# S8254A-HY2213-4S.net
KiCad netlist of a schematic drawn in EAGLE
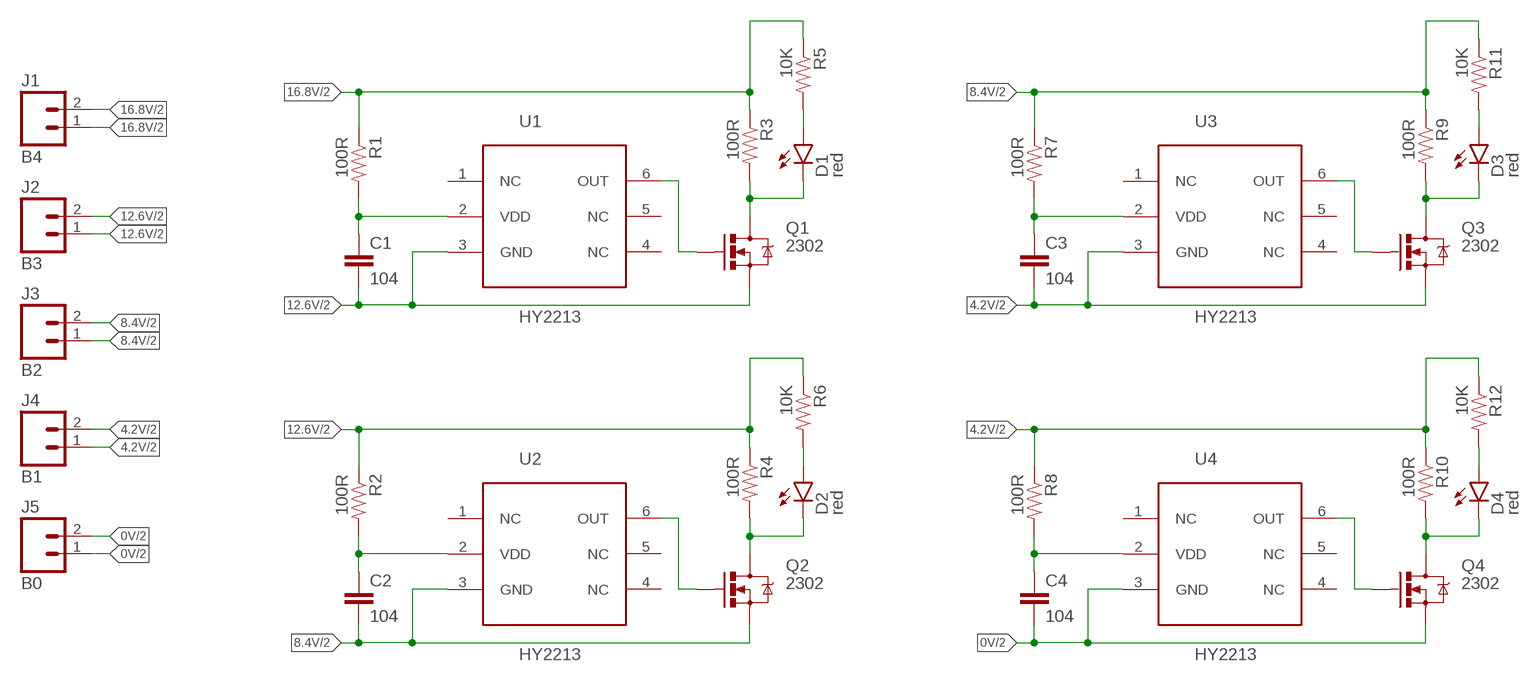
[diagram p0: schematic, sheet 1]
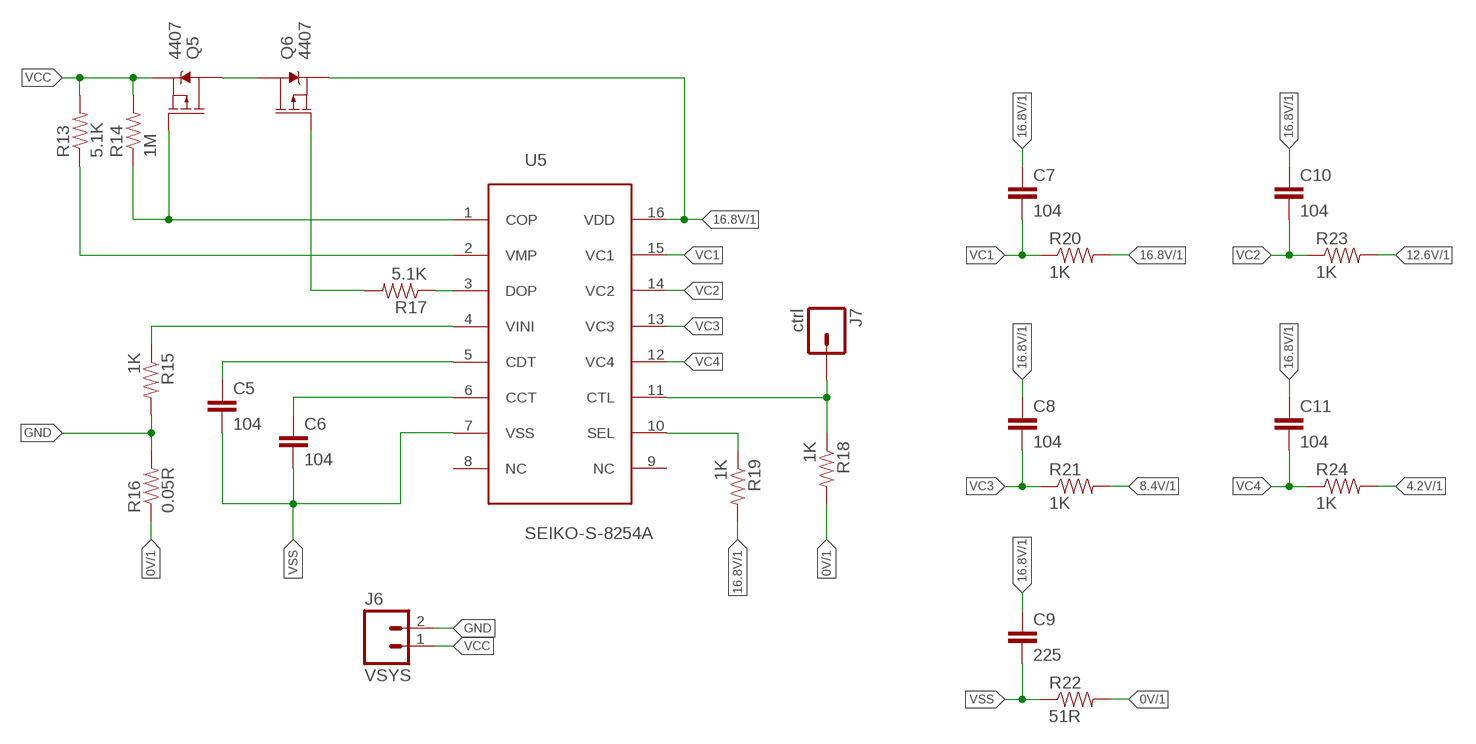
[diagram p1: schematic, sheet 2]

(export (version "E")
  (design (tool "Eeschema 10.0.6"))
  (components
    (comp (ref "C5")
      (value "104")
      (footprint "eagle-import:0603-CAP")
      (libsource (lib "eagle-import") (part "CAP0603-CAP"))
    )
    (comp (ref "C6")
      (value "104")
      (footprint "eagle-import:0603-CAP")
      (libsource (lib "eagle-import") (part "CAP0603-CAP"))
    )
    (comp (ref "C7")
      (value "104")
      (footprint "eagle-import:0603-CAP")
      (libsource (lib "eagle-import") (part "CAP0603-CAP"))
    )
    (comp (ref "C8")
      (value "104")
      (footprint "eagle-import:0603-CAP")
      (libsource (lib "eagle-import") (part "CAP0603-CAP"))
    )
    (comp (ref "C9")
      (value "225")
      (footprint "eagle-import:0603-CAP")
      (libsource (lib "eagle-import") (part "CAP0603-CAP"))
    )
    (comp (ref "C10")
      (value "104")
      (footprint "eagle-import:0603-CAP")
      (libsource (lib "eagle-import") (part "CAP0603-CAP"))
    )
    (comp (ref "C11")
      (value "104")
      (footprint "eagle-import:0603-CAP")
      (libsource (lib "eagle-import") (part "CAP0603-CAP"))
    )
    (comp (ref "J6")
      (value "VSYS")
      (footprint "eagle-import:1X02_NO_SILK")
      (libsource (lib "eagle-import") (part "M021X02_NO_SILK"))
    )
    (comp (ref "J7")
      (value "ctrl")
      (footprint "eagle-import:1X01")
      (libsource (lib "eagle-import") (part "M01PTH"))
    )
    (comp (ref "Q5")
      (value "4407")
      (footprint "eagle-import:SO08")
      (libsource (lib "eagle-import") (part "MOSFET_PCH-NDS8434"))
    )
    (comp (ref "Q6")
      (value "4407")
      (footprint "eagle-import:SO08")
      (libsource (lib "eagle-import") (part "MOSFET_PCH-NDS8434"))
    )
    (comp (ref "R13")
      (value "5.1K")
      (footprint "eagle-import:0603-RES")
      (libsource (lib "eagle-import") (part "RESISTOR0603"))
    )
    (comp (ref "R14")
      (value "1M")
      (footprint "eagle-import:0603-RES")
      (libsource (lib "eagle-import") (part "RESISTOR0603"))
    )
    (comp (ref "R15")
      (value "1K")
      (footprint "eagle-import:0603-RES")
      (libsource (lib "eagle-import") (part "RESISTOR0603"))
    )
    (comp (ref "R16")
      (value "0.05R")
      (footprint "eagle-import:R2512")
      (libsource (lib "eagle-import") (part "RESISTOR2512"))
    )
    (comp (ref "R17")
      (value "5.1K")
      (footprint "eagle-import:0603-RES")
      (libsource (lib "eagle-import") (part "RESISTOR0603"))
    )
    (comp (ref "R18")
      (value "1K")
      (footprint "eagle-import:0603-RES")
      (libsource (lib "eagle-import") (part "RESISTOR0603"))
    )
    (comp (ref "R19")
      (value "1K")
      (footprint "eagle-import:0603-RES")
      (libsource (lib "eagle-import") (part "RESISTOR0603"))
    )
    (comp (ref "R20")
      (value "1K")
      (footprint "eagle-import:0603-RES")
      (libsource (lib "eagle-import") (part "RESISTOR0603"))
    )
    (comp (ref "R21")
      (value "1K")
      (footprint "eagle-import:0603-RES")
      (libsource (lib "eagle-import") (part "RESISTOR0603"))
    )
    (comp (ref "R22")
      (value "51R")
      (footprint "eagle-import:0603-RES")
      (libsource (lib "eagle-import") (part "RESISTOR0603"))
    )
    (comp (ref "R23")
      (value "1K")
      (footprint "eagle-import:0603-RES")
      (libsource (lib "eagle-import") (part "RESISTOR0603"))
    )
    (comp (ref "R24")
      (value "1K")
      (footprint "eagle-import:0603-RES")
      (libsource (lib "eagle-import") (part "RESISTOR0603"))
    )
    (comp (ref "U5")
      (value "SEIKO-S-8254A")
      (footprint "eagle-import:TSSOP16")
      (libsource (lib "eagle-import") (part "SEIKO-S-8254A"))
    )
    (comp (ref "C1")
      (value "104")
      (footprint "eagle-import:0603-CAP")
      (libsource (lib "eagle-import") (part "CAP0603-CAP"))
    )
    (comp (ref "C2")
      (value "104")
      (footprint "eagle-import:0603-CAP")
      (libsource (lib "eagle-import") (part "CAP0603-CAP"))
    )
    (comp (ref "C3")
      (value "104")
      (footprint "eagle-import:0603-CAP")
      (libsource (lib "eagle-import") (part "CAP0603-CAP"))
    )
    (comp (ref "C4")
      (value "104")
      (footprint "eagle-import:0603-CAP")
      (libsource (lib "eagle-import") (part "CAP0603-CAP"))
    )
    (comp (ref "D1")
      (value "red")
      (footprint "eagle-import:LED-0603-SEEED")
      (libsource (lib "eagle-import") (part "LED-SEEED-0603"))
    )
    (comp (ref "D2")
      (value "red")
      (footprint "eagle-import:LED-0603-SEEED")
      (libsource (lib "eagle-import") (part "LED-SEEED-0603"))
    )
    (comp (ref "D3")
      (value "red")
      (footprint "eagle-import:LED-0603-SEEED")
      (libsource (lib "eagle-import") (part "LED-SEEED-0603"))
    )
    (comp (ref "D4")
      (value "red")
      (footprint "eagle-import:LED-0603-SEEED")
      (libsource (lib "eagle-import") (part "LED-SEEED-0603"))
    )
    (comp (ref "J1")
      (value "B4")
      (footprint "eagle-import:1X02_NO_SILK")
      (libsource (lib "eagle-import") (part "M021X02_NO_SILK"))
    )
    (comp (ref "J2")
      (value "B3")
      (footprint "eagle-import:1X02_NO_SILK")
      (libsource (lib "eagle-import") (part "M021X02_NO_SILK"))
    )
    (comp (ref "J3")
      (value "B2")
      (footprint "eagle-import:1X02_NO_SILK")
      (libsource (lib "eagle-import") (part "M021X02_NO_SILK"))
    )
    (comp (ref "J4")
      (value "B1")
      (footprint "eagle-import:1X02_NO_SILK")
      (libsource (lib "eagle-import") (part "M021X02_NO_SILK"))
    )
    (comp (ref "J5")
      (value "B0")
      (footprint "eagle-import:1X02_NO_SILK")
      (libsource (lib "eagle-import") (part "M021X02_NO_SILK"))
    )
    (comp (ref "Q1")
      (value "2302")
      (footprint "eagle-import:SOT23-3")
      (libsource (lib "eagle-import") (part "MOSFET-NCHANNELAO3404A"))
    )
    (comp (ref "Q2")
      (value "2302")
      (footprint "eagle-import:SOT23-3")
      (libsource (lib "eagle-import") (part "MOSFET-NCHANNELAO3404A"))
    )
    (comp (ref "Q3")
      (value "2302")
      (footprint "eagle-import:SOT23-3")
      (libsource (lib "eagle-import") (part "MOSFET-NCHANNELAO3404A"))
    )
    (comp (ref "Q4")
      (value "2302")
      (footprint "eagle-import:SOT23-3")
      (libsource (lib "eagle-import") (part "MOSFET-NCHANNELAO3404A"))
    )
    (comp (ref "R1")
      (value "100R")
      (footprint "eagle-import:0603-RES")
      (libsource (lib "eagle-import") (part "RESISTOR0603"))
    )
    (comp (ref "R2")
      (value "100R")
      (footprint "eagle-import:0603-RES")
      (libsource (lib "eagle-import") (part "RESISTOR0603"))
    )
    (comp (ref "R3")
      (value "100R")
      (footprint "eagle-import:R2512")
      (libsource (lib "eagle-import") (part "RESISTOR2512"))
    )
    (comp (ref "R4")
      (value "100R")
      (footprint "eagle-import:R2512")
      (libsource (lib "eagle-import") (part "RESISTOR2512"))
    )
    (comp (ref "R5")
      (value "10K")
      (footprint "eagle-import:0603-RES")
      (libsource (lib "eagle-import") (part "RESISTOR0603"))
    )
    (comp (ref "R6")
      (value "10K")
      (footprint "eagle-import:0603-RES")
      (libsource (lib "eagle-import") (part "RESISTOR0603"))
    )
    (comp (ref "R7")
      (value "100R")
      (footprint "eagle-import:0603-RES")
      (libsource (lib "eagle-import") (part "RESISTOR0603"))
    )
    (comp (ref "R8")
      (value "100R")
      (footprint "eagle-import:0603-RES")
      (libsource (lib "eagle-import") (part "RESISTOR0603"))
    )
    (comp (ref "R9")
      (value "100R")
      (footprint "eagle-import:R2512")
      (libsource (lib "eagle-import") (part "RESISTOR2512"))
    )
    (comp (ref "R10")
      (value "100R")
      (footprint "eagle-import:R2512")
      (libsource (lib "eagle-import") (part "RESISTOR2512"))
    )
    (comp (ref "R11")
      (value "10K")
      (footprint "eagle-import:0603-RES")
      (libsource (lib "eagle-import") (part "RESISTOR0603"))
    )
    (comp (ref "R12")
      (value "10K")
      (footprint "eagle-import:0603-RES")
      (libsource (lib "eagle-import") (part "RESISTOR0603"))
    )
    (comp (ref "U1")
      (value "HY2213")
      (footprint "eagle-import:SOT23-6")
      (libsource (lib "eagle-import") (part "HY2213"))
    )
    (comp (ref "U2")
      (value "HY2213")
      (footprint "eagle-import:SOT23-6")
      (libsource (lib "eagle-import") (part "HY2213"))
    )
    (comp (ref "U3")
      (value "HY2213")
      (footprint "eagle-import:SOT23-6")
      (libsource (lib "eagle-import") (part "HY2213"))
    )
    (comp (ref "U4")
      (value "HY2213")
      (footprint "eagle-import:SOT23-6")
      (libsource (lib "eagle-import") (part "HY2213"))
    )
  )
  (nets
    (net (code "1") (name "0V") (class "Default")
      (node (ref "C4") (pin "2") (pinfunction "2_2") (pintype "passive"))
      (node (ref "J5") (pin "1") (pinfunction "1_1") (pintype "passive"))
      (node (ref "J5") (pin "2") (pinfunction "2_2") (pintype "passive"))
      (node (ref "Q4") (pin "2") (pinfunction "S_2") (pintype "passive"))
      (node (ref "R16") (pin "1") (pinfunction "1_1") (pintype "passive"))
      (node (ref "R18") (pin "2") (pinfunction "2_2") (pintype "passive"))
      (node (ref "R22") (pin "2") (pinfunction "2_2") (pintype "passive"))
      (node (ref "U4") (pin "3") (pinfunction "GND_3") (pintype "bidirectional"))
    )
    (net (code "2") (name "4.2V") (class "Default")
      (node (ref "C3") (pin "2") (pinfunction "2_2") (pintype "passive"))
      (node (ref "J4") (pin "1") (pinfunction "1_1") (pintype "passive"))
      (node (ref "J4") (pin "2") (pinfunction "2_2") (pintype "passive"))
      (node (ref "Q3") (pin "2") (pinfunction "S_2") (pintype "passive"))
      (node (ref "R10") (pin "1") (pinfunction "1_1") (pintype "passive"))
      (node (ref "R12") (pin "1") (pinfunction "1_1") (pintype "passive"))
      (node (ref "R24") (pin "2") (pinfunction "2_2") (pintype "passive"))
      (node (ref "R8") (pin "1") (pinfunction "1_1") (pintype "passive"))
      (node (ref "U3") (pin "3") (pinfunction "GND_3") (pintype "bidirectional"))
    )
    (net (code "3") (name "8.4V") (class "Default")
      (node (ref "C2") (pin "2") (pinfunction "2_2") (pintype "passive"))
      (node (ref "J3") (pin "1") (pinfunction "1_1") (pintype "passive"))
      (node (ref "J3") (pin "2") (pinfunction "2_2") (pintype "passive"))
      (node (ref "Q2") (pin "2") (pinfunction "S_2") (pintype "passive"))
      (node (ref "R11") (pin "1") (pinfunction "1_1") (pintype "passive"))
      (node (ref "R21") (pin "2") (pinfunction "2_2") (pintype "passive"))
      (node (ref "R7") (pin "1") (pinfunction "1_1") (pintype "passive"))
      (node (ref "R9") (pin "1") (pinfunction "1_1") (pintype "passive"))
      (node (ref "U2") (pin "3") (pinfunction "GND_3") (pintype "bidirectional"))
    )
    (net (code "4") (name "12.6V") (class "Default")
      (node (ref "C1") (pin "2") (pinfunction "2_2") (pintype "passive"))
      (node (ref "J2") (pin "1") (pinfunction "1_1") (pintype "passive"))
      (node (ref "J2") (pin "2") (pinfunction "2_2") (pintype "passive"))
      (node (ref "Q1") (pin "2") (pinfunction "S_2") (pintype "passive"))
      (node (ref "R2") (pin "1") (pinfunction "1_1") (pintype "passive"))
      (node (ref "R23") (pin "2") (pinfunction "2_2") (pintype "passive"))
      (node (ref "R4") (pin "1") (pinfunction "1_1") (pintype "passive"))
      (node (ref "R6") (pin "1") (pinfunction "1_1") (pintype "passive"))
      (node (ref "U1") (pin "3") (pinfunction "GND_3") (pintype "bidirectional"))
    )
    (net (code "5") (name "16.8V") (class "Default")
      (node (ref "C10") (pin "1") (pinfunction "1_1") (pintype "passive"))
      (node (ref "C11") (pin "1") (pinfunction "1_1") (pintype "passive"))
      (node (ref "C7") (pin "1") (pinfunction "1_1") (pintype "passive"))
      (node (ref "C8") (pin "1") (pinfunction "1_1") (pintype "passive"))
      (node (ref "C9") (pin "1") (pinfunction "1_1") (pintype "passive"))
      (node (ref "J1") (pin "1") (pinfunction "1_1") (pintype "passive"))
      (node (ref "J1") (pin "2") (pinfunction "2_2") (pintype "passive"))
      (node (ref "Q6") (pin "1") (pinfunction "S_1") (pintype "bidirectional"))
      (node (ref "Q6") (pin "2") (pinfunction "S_2") (pintype "bidirectional"))
      (node (ref "Q6") (pin "3") (pinfunction "S_3") (pintype "bidirectional"))
      (node (ref "R1") (pin "1") (pinfunction "1_1") (pintype "passive"))
      (node (ref "R19") (pin "2") (pinfunction "2_2") (pintype "passive"))
      (node (ref "R20") (pin "2") (pinfunction "2_2") (pintype "passive"))
      (node (ref "R3") (pin "1") (pinfunction "1_1") (pintype "passive"))
      (node (ref "R5") (pin "1") (pinfunction "1_1") (pintype "passive"))
      (node (ref "U5") (pin "16") (pinfunction "VDD_16") (pintype "bidirectional"))
    )
    (net (code "6") (name "GND") (class "Default")
      (node (ref "J6") (pin "2") (pinfunction "2_2") (pintype "passive"))
      (node (ref "R15") (pin "2") (pinfunction "2_2") (pintype "passive"))
      (node (ref "R16") (pin "2") (pinfunction "2_2") (pintype "passive"))
    )
    (net (code "7") (name "Net-(D1-A)") (class "Default")
      (node (ref "D1") (pin "+") (pinfunction "A_+") (pintype "passive"))
      (node (ref "R5") (pin "2") (pinfunction "2_2") (pintype "passive"))
    )
    (net (code "8") (name "Net-(D1-C)") (class "Default")
      (node (ref "D1") (pin "-") (pinfunction "C_-") (pintype "passive"))
      (node (ref "Q1") (pin "3") (pinfunction "D_3") (pintype "passive"))
      (node (ref "R3") (pin "2") (pinfunction "2_2") (pintype "passive"))
    )
    (net (code "9") (name "Net-(D2-A)") (class "Default")
      (node (ref "D2") (pin "+") (pinfunction "A_+") (pintype "passive"))
      (node (ref "R6") (pin "2") (pinfunction "2_2") (pintype "passive"))
    )
    (net (code "10") (name "Net-(D2-C)") (class "Default")
      (node (ref "D2") (pin "-") (pinfunction "C_-") (pintype "passive"))
      (node (ref "Q2") (pin "3") (pinfunction "D_3") (pintype "passive"))
      (node (ref "R4") (pin "2") (pinfunction "2_2") (pintype "passive"))
    )
    (net (code "11") (name "Net-(D3-A)") (class "Default")
      (node (ref "D3") (pin "+") (pinfunction "A_+") (pintype "passive"))
      (node (ref "R11") (pin "2") (pinfunction "2_2") (pintype "passive"))
    )
    (net (code "12") (name "Net-(D3-C)") (class "Default")
      (node (ref "D3") (pin "-") (pinfunction "C_-") (pintype "passive"))
      (node (ref "Q3") (pin "3") (pinfunction "D_3") (pintype "passive"))
      (node (ref "R9") (pin "2") (pinfunction "2_2") (pintype "passive"))
    )
    (net (code "13") (name "Net-(D4-A)") (class "Default")
      (node (ref "D4") (pin "+") (pinfunction "A_+") (pintype "passive"))
      (node (ref "R12") (pin "2") (pinfunction "2_2") (pintype "passive"))
    )
    (net (code "14") (name "Net-(D4-C)") (class "Default")
      (node (ref "D4") (pin "-") (pinfunction "C_-") (pintype "passive"))
      (node (ref "Q4") (pin "3") (pinfunction "D_3") (pintype "passive"))
      (node (ref "R10") (pin "2") (pinfunction "2_2") (pintype "passive"))
    )
    (net (code "15") (name "Net-(Q1-G)") (class "Default")
      (node (ref "Q1") (pin "1") (pinfunction "G_1") (pintype "passive"))
      (node (ref "U1") (pin "6") (pinfunction "OUT_6") (pintype "bidirectional"))
    )
    (net (code "16") (name "Net-(Q2-G)") (class "Default")
      (node (ref "Q2") (pin "1") (pinfunction "G_1") (pintype "passive"))
      (node (ref "U2") (pin "6") (pinfunction "OUT_6") (pintype "bidirectional"))
    )
    (net (code "17") (name "Net-(Q3-G)") (class "Default")
      (node (ref "Q3") (pin "1") (pinfunction "G_1") (pintype "passive"))
      (node (ref "U3") (pin "6") (pinfunction "OUT_6") (pintype "bidirectional"))
    )
    (net (code "18") (name "Net-(Q4-G)") (class "Default")
      (node (ref "Q4") (pin "1") (pinfunction "G_1") (pintype "passive"))
      (node (ref "U4") (pin "6") (pinfunction "OUT_6") (pintype "bidirectional"))
    )
    (net (code "19") (name "Net-(Q5-D-Pad5)") (class "Default")
      (node (ref "Q5") (pin "5") (pinfunction "D_5") (pintype "bidirectional"))
      (node (ref "Q5") (pin "6") (pinfunction "D_6") (pintype "bidirectional"))
      (node (ref "Q5") (pin "7") (pinfunction "D_7") (pintype "bidirectional"))
      (node (ref "Q5") (pin "8") (pinfunction "D_8") (pintype "bidirectional"))
      (node (ref "Q6") (pin "5") (pinfunction "D_5") (pintype "bidirectional"))
      (node (ref "Q6") (pin "6") (pinfunction "D_6") (pintype "bidirectional"))
      (node (ref "Q6") (pin "7") (pinfunction "D_7") (pintype "bidirectional"))
      (node (ref "Q6") (pin "8") (pinfunction "D_8") (pintype "bidirectional"))
    )
    (net (code "20") (name "Net-(Q5-G)") (class "Default")
      (node (ref "Q5") (pin "4") (pinfunction "G_4") (pintype "bidirectional"))
      (node (ref "R14") (pin "1") (pinfunction "1_1") (pintype "passive"))
      (node (ref "U5") (pin "1") (pinfunction "COP_1") (pintype "bidirectional"))
    )
    (net (code "21") (name "Net-(Q6-G)") (class "Default")
      (node (ref "Q6") (pin "4") (pinfunction "G_4") (pintype "bidirectional"))
      (node (ref "R17") (pin "2") (pinfunction "2_2") (pintype "passive"))
    )
    (net (code "22") (name "Net-(U1-VDD)") (class "Default")
      (node (ref "C1") (pin "1") (pinfunction "1_1") (pintype "passive"))
      (node (ref "R1") (pin "2") (pinfunction "2_2") (pintype "passive"))
      (node (ref "U1") (pin "2") (pinfunction "VDD_2") (pintype "bidirectional"))
    )
    (net (code "23") (name "Net-(U2-VDD)") (class "Default")
      (node (ref "C2") (pin "1") (pinfunction "1_1") (pintype "passive"))
      (node (ref "R2") (pin "2") (pinfunction "2_2") (pintype "passive"))
      (node (ref "U2") (pin "2") (pinfunction "VDD_2") (pintype "bidirectional"))
    )
    (net (code "24") (name "Net-(U3-VDD)") (class "Default")
      (node (ref "C3") (pin "1") (pinfunction "1_1") (pintype "passive"))
      (node (ref "R7") (pin "2") (pinfunction "2_2") (pintype "passive"))
      (node (ref "U3") (pin "2") (pinfunction "VDD_2") (pintype "bidirectional"))
    )
    (net (code "25") (name "Net-(U4-VDD)") (class "Default")
      (node (ref "C4") (pin "1") (pinfunction "1_1") (pintype "passive"))
      (node (ref "R8") (pin "2") (pinfunction "2_2") (pintype "passive"))
      (node (ref "U4") (pin "2") (pinfunction "VDD_2") (pintype "bidirectional"))
    )
    (net (code "26") (name "Net-(U5-CCT)") (class "Default")
      (node (ref "C6") (pin "1") (pinfunction "1_1") (pintype "passive"))
      (node (ref "U5") (pin "6") (pinfunction "CCT_6") (pintype "bidirectional"))
    )
    (net (code "27") (name "Net-(U5-CDT)") (class "Default")
      (node (ref "C5") (pin "1") (pinfunction "1_1") (pintype "passive"))
      (node (ref "U5") (pin "5") (pinfunction "CDT_5") (pintype "bidirectional"))
    )
    (net (code "28") (name "Net-(U5-CTL)") (class "Default")
      (node (ref "J7") (pin "1") (pinfunction "1_1") (pintype "passive"))
      (node (ref "R18") (pin "1") (pinfunction "1_1") (pintype "passive"))
      (node (ref "U5") (pin "11") (pinfunction "CTL_11") (pintype "bidirectional"))
    )
    (net (code "29") (name "Net-(U5-DOP)") (class "Default")
      (node (ref "R17") (pin "1") (pinfunction "1_1") (pintype "passive"))
      (node (ref "U5") (pin "3") (pinfunction "DOP_3") (pintype "bidirectional"))
    )
    (net (code "30") (name "Net-(U5-SEL)") (class "Default")
      (node (ref "R19") (pin "1") (pinfunction "1_1") (pintype "passive"))
      (node (ref "U5") (pin "10") (pinfunction "SEL_10") (pintype "bidirectional"))
    )
    (net (code "31") (name "Net-(U5-VINI)") (class "Default")
      (node (ref "R15") (pin "1") (pinfunction "1_1") (pintype "passive"))
      (node (ref "U5") (pin "4") (pinfunction "VINI_4") (pintype "bidirectional"))
    )
    (net (code "32") (name "Net-(U5-VMP)") (class "Default")
      (node (ref "R13") (pin "1") (pinfunction "1_1") (pintype "passive"))
      (node (ref "U5") (pin "2") (pinfunction "VMP_2") (pintype "bidirectional"))
    )
    (net (code "33") (name "VC1") (class "Default")
      (node (ref "C7") (pin "2") (pinfunction "2_2") (pintype "passive"))
      (node (ref "R20") (pin "1") (pinfunction "1_1") (pintype "passive"))
      (node (ref "U5") (pin "15") (pinfunction "VC1_15") (pintype "bidirectional"))
    )
    (net (code "34") (name "VC2") (class "Default")
      (node (ref "C10") (pin "2") (pinfunction "2_2") (pintype "passive"))
      (node (ref "R23") (pin "1") (pinfunction "1_1") (pintype "passive"))
      (node (ref "U5") (pin "14") (pinfunction "VC2_14") (pintype "bidirectional"))
    )
    (net (code "35") (name "VC3") (class "Default")
      (node (ref "C8") (pin "2") (pinfunction "2_2") (pintype "passive"))
      (node (ref "R21") (pin "1") (pinfunction "1_1") (pintype "passive"))
      (node (ref "U5") (pin "13") (pinfunction "VC3_13") (pintype "bidirectional"))
    )
    (net (code "36") (name "VC4") (class "Default")
      (node (ref "C11") (pin "2") (pinfunction "2_2") (pintype "passive"))
      (node (ref "R24") (pin "1") (pinfunction "1_1") (pintype "passive"))
      (node (ref "U5") (pin "12") (pinfunction "VC4_12") (pintype "bidirectional"))
    )
    (net (code "37") (name "VCC") (class "Default")
      (node (ref "J6") (pin "1") (pinfunction "1_1") (pintype "passive"))
      (node (ref "Q5") (pin "1") (pinfunction "S_1") (pintype "bidirectional"))
      (node (ref "Q5") (pin "2") (pinfunction "S_2") (pintype "bidirectional"))
      (node (ref "Q5") (pin "3") (pinfunction "S_3") (pintype "bidirectional"))
      (node (ref "R13") (pin "2") (pinfunction "2_2") (pintype "passive"))
      (node (ref "R14") (pin "2") (pinfunction "2_2") (pintype "passive"))
    )
    (net (code "38") (name "VSS") (class "Default")
      (node (ref "C5") (pin "2") (pinfunction "2_2") (pintype "passive"))
      (node (ref "C6") (pin "2") (pinfunction "2_2") (pintype "passive"))
      (node (ref "C9") (pin "2") (pinfunction "2_2") (pintype "passive"))
      (node (ref "R22") (pin "1") (pinfunction "1_1") (pintype "passive"))
      (node (ref "U5") (pin "7") (pinfunction "VSS_7") (pintype "bidirectional"))
    )
    (net (code "39") (name "unconnected-(U1-NC-Pad1)") (class "Default")
      (node (ref "U1") (pin "1") (pinfunction "NC_1") (pintype "bidirectional"))
    )
    (net (code "40") (name "unconnected-(U1-NC-Pad4)") (class "Default")
      (node (ref "U1") (pin "4") (pinfunction "NC_4") (pintype "bidirectional"))
    )
    (net (code "41") (name "unconnected-(U1-NC-Pad5)") (class "Default")
      (node (ref "U1") (pin "5") (pinfunction "NC_5") (pintype "bidirectional"))
    )
    (net (code "42") (name "unconnected-(U2-NC-Pad1)") (class "Default")
      (node (ref "U2") (pin "1") (pinfunction "NC_1") (pintype "bidirectional"))
    )
    (net (code "43") (name "unconnected-(U2-NC-Pad4)") (class "Default")
      (node (ref "U2") (pin "4") (pinfunction "NC_4") (pintype "bidirectional"))
    )
    (net (code "44") (name "unconnected-(U2-NC-Pad5)") (class "Default")
      (node (ref "U2") (pin "5") (pinfunction "NC_5") (pintype "bidirectional"))
    )
    (net (code "45") (name "unconnected-(U3-NC-Pad1)") (class "Default")
      (node (ref "U3") (pin "1") (pinfunction "NC_1") (pintype "bidirectional"))
    )
    (net (code "46") (name "unconnected-(U3-NC-Pad4)") (class "Default")
      (node (ref "U3") (pin "4") (pinfunction "NC_4") (pintype "bidirectional"))
    )
    (net (code "47") (name "unconnected-(U3-NC-Pad5)") (class "Default")
      (node (ref "U3") (pin "5") (pinfunction "NC_5") (pintype "bidirectional"))
    )
    (net (code "48") (name "unconnected-(U4-NC-Pad1)") (class "Default")
      (node (ref "U4") (pin "1") (pinfunction "NC_1") (pintype "bidirectional"))
    )
    (net (code "49") (name "unconnected-(U4-NC-Pad4)") (class "Default")
      (node (ref "U4") (pin "4") (pinfunction "NC_4") (pintype "bidirectional"))
    )
    (net (code "50") (name "unconnected-(U4-NC-Pad5)") (class "Default")
      (node (ref "U4") (pin "5") (pinfunction "NC_5") (pintype "bidirectional"))
    )
    (net (code "51") (name "unconnected-(U5-NC-Pad8)") (class "Default")
      (node (ref "U5") (pin "8") (pinfunction "NC_8") (pintype "bidirectional"))
    )
    (net (code "52") (name "unconnected-(U5-NC-Pad9)") (class "Default")
      (node (ref "U5") (pin "9") (pinfunction "NC_9") (pintype "bidirectional"))
    )
  )
)
